# Power2.net
KiCad netlist of a schematic drawn in Altium Designer
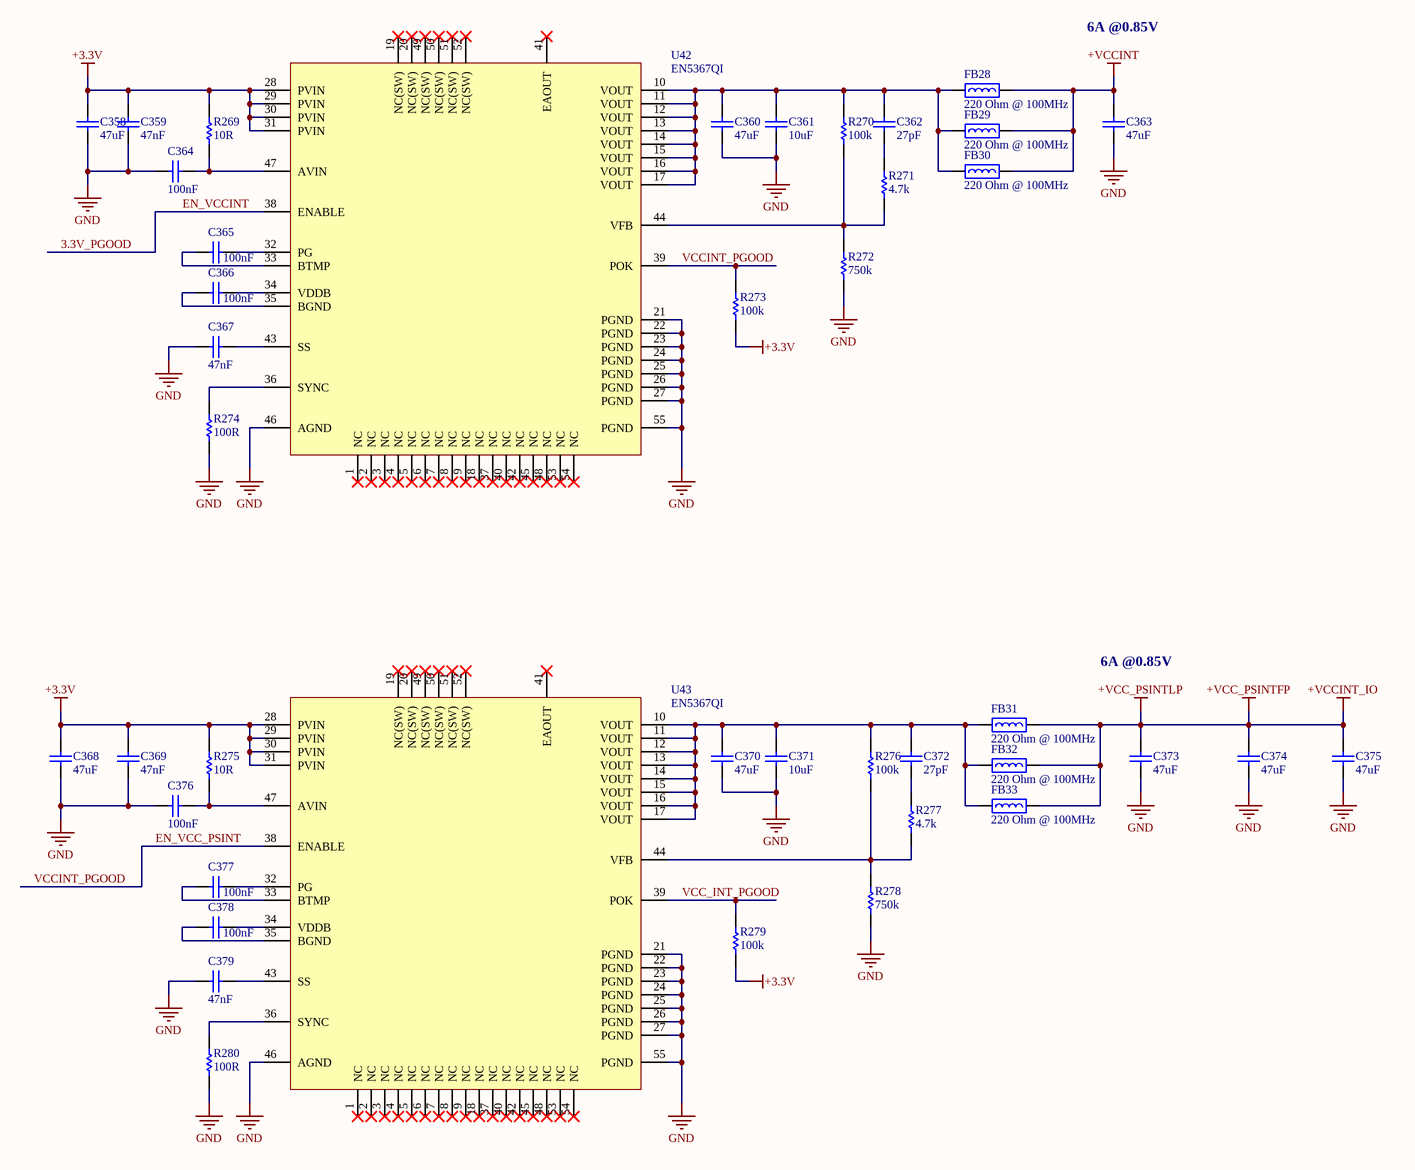
[diagram p0: Power2.SchDoc]

(export (version "E")
  (design (tool "Eeschema 10.0.6"))
  (components
    (comp (ref "C358")
      (value "47uF")
      (footprint "CAPC3216L_1206")
      (description "CAP CER 47UF 25V X5R 1206")
      (fields (field (name "VOLTAGE") "25V") (field (name "TOLERANCE") "20%"))
      (libsource (lib "Ultrascale_SchLib") (part "CAPCER1206X5R47U25V_20T"))
    )
    (comp (ref "C359")
      (value "47nF")
      (footprint "CAPC2012L_0805")
      (description "CAP CER 0.047UF 50V X7R 0805")
      (fields (field (name "VOLTAGE") "50V") (field (name "TOLERANCE") "10%"))
      (libsource (lib "Ultrascale_SchLib") (part "CAPCER0805X5R47N50V_10T"))
    )
    (comp (ref "C360")
      (value "47uF")
      (footprint "CAPC3216L_1206")
      (description "CAP CER 47UF 25V X5R 1206")
      (fields (field (name "VOLTAGE") "25V") (field (name "TOLERANCE") "20%"))
      (libsource (lib "Ultrascale_SchLib") (part "CAPCER1206X5R47U25V_20T"))
    )
    (comp (ref "C361")
      (value "10uF")
      (footprint "CAPC1005L_0402")
      (description "CAP CER 10UF 10V X5R 0402")
      (fields (field (name "VOLTAGE") "10V") (field (name "TOLERANCE") "20%"))
      (libsource (lib "Ultrascale_SchLib") (part "CAPCER0402X5R10U10V_20T"))
    )
    (comp (ref "C362")
      (value "27pF")
      (footprint "CAPC1005L_0402")
      (description "CAP CER 27PF 50V C0G/NP0 0402")
      (fields (field (name "VOLTAGE") "50V") (field (name "TOLERANCE") "5%"))
      (libsource (lib "Ultrascale_SchLib") (part "CAPCER0402C0G27P50V_5T"))
    )
    (comp (ref "C363")
      (value "47uF")
      (footprint "CAPC3216L_1206")
      (description "CAP CER 47UF 25V X5R 1206")
      (fields (field (name "VOLTAGE") "25V") (field (name "TOLERANCE") "20%"))
      (libsource (lib "Ultrascale_SchLib") (part "CAPCER1206X5R47U25V_20T"))
    )
    (comp (ref "C364")
      (value "100nF")
      (footprint "CAPC1005L_0402")
      (description "CAP CER 0.1UF 25V X7R 0402")
      (fields (field (name "VOLTAGE") "25V") (field (name "TOLERANCE") "10%"))
      (libsource (lib "Ultrascale_SchLib") (part "CAPCER0402X7R100N25V_10T"))
    )
    (comp (ref "C365")
      (value "100nF")
      (footprint "CAPC1005L_0402")
      (description "CAP CER 0.1UF 25V X7R 0402")
      (fields (field (name "VOLTAGE") "25V") (field (name "TOLERANCE") "10%"))
      (libsource (lib "Ultrascale_SchLib") (part "CAPCER0402X7R100N25V_10T"))
    )
    (comp (ref "C366")
      (value "100nF")
      (footprint "CAPC1005L_0402")
      (description "CAP CER 0.1UF 25V X7R 0402")
      (fields (field (name "VOLTAGE") "25V") (field (name "TOLERANCE") "10%"))
      (libsource (lib "Ultrascale_SchLib") (part "CAPCER0402X7R100N25V_10T"))
    )
    (comp (ref "C367")
      (value "47nF")
      (footprint "CAPC2012L_0805")
      (description "CAP CER 0.047UF 50V X7R 0805")
      (fields (field (name "VOLTAGE") "50V") (field (name "TOLERANCE") "10%"))
      (libsource (lib "Ultrascale_SchLib") (part "CAPCER0805X5R47N50V_10T"))
    )
    (comp (ref "C368")
      (value "47uF")
      (footprint "CAPC3216L_1206")
      (description "CAP CER 47UF 25V X5R 1206")
      (fields (field (name "VOLTAGE") "25V") (field (name "TOLERANCE") "20%"))
      (libsource (lib "Ultrascale_SchLib") (part "CAPCER1206X5R47U25V_20T"))
    )
    (comp (ref "C369")
      (value "47nF")
      (footprint "CAPC2012L_0805")
      (description "CAP CER 0.047UF 50V X7R 0805")
      (fields (field (name "VOLTAGE") "50V") (field (name "TOLERANCE") "10%"))
      (libsource (lib "Ultrascale_SchLib") (part "CAPCER0805X5R47N50V_10T"))
    )
    (comp (ref "C370")
      (value "47uF")
      (footprint "CAPC3216L_1206")
      (description "CAP CER 47UF 25V X5R 1206")
      (fields (field (name "VOLTAGE") "25V") (field (name "TOLERANCE") "20%"))
      (libsource (lib "Ultrascale_SchLib") (part "CAPCER1206X5R47U25V_20T"))
    )
    (comp (ref "C371")
      (value "10uF")
      (footprint "CAPC1005L_0402")
      (description "CAP CER 10UF 10V X5R 0402")
      (fields (field (name "VOLTAGE") "10V") (field (name "TOLERANCE") "20%"))
      (libsource (lib "Ultrascale_SchLib") (part "CAPCER0402X5R10U10V_20T"))
    )
    (comp (ref "C372")
      (value "27pF")
      (footprint "CAPC1005L_0402")
      (description "CAP CER 27PF 50V C0G/NP0 0402")
      (fields (field (name "VOLTAGE") "50V") (field (name "TOLERANCE") "5%"))
      (libsource (lib "Ultrascale_SchLib") (part "CAPCER0402C0G27P50V_5T"))
    )
    (comp (ref "C373")
      (value "47uF")
      (footprint "CAPC3216L_1206")
      (description "CAP CER 47UF 25V X5R 1206")
      (fields (field (name "VOLTAGE") "25V") (field (name "TOLERANCE") "20%"))
      (libsource (lib "Ultrascale_SchLib") (part "CAPCER1206X5R47U25V_20T"))
    )
    (comp (ref "C374")
      (value "47uF")
      (footprint "CAPC3216L_1206")
      (description "CAP CER 47UF 25V X5R 1206")
      (fields (field (name "VOLTAGE") "25V") (field (name "TOLERANCE") "20%"))
      (libsource (lib "Ultrascale_SchLib") (part "CAPCER1206X5R47U25V_20T"))
    )
    (comp (ref "C375")
      (value "47uF")
      (footprint "CAPC3216L_1206")
      (description "CAP CER 47UF 25V X5R 1206")
      (fields (field (name "VOLTAGE") "25V") (field (name "TOLERANCE") "20%"))
      (libsource (lib "Ultrascale_SchLib") (part "CAPCER1206X5R47U25V_20T"))
    )
    (comp (ref "C376")
      (value "100nF")
      (footprint "CAPC1005L_0402")
      (description "CAP CER 0.1UF 25V X7R 0402")
      (fields (field (name "VOLTAGE") "25V") (field (name "TOLERANCE") "10%"))
      (libsource (lib "Ultrascale_SchLib") (part "CAPCER0402X7R100N25V_10T"))
    )
    (comp (ref "C377")
      (value "100nF")
      (footprint "CAPC1005L_0402")
      (description "CAP CER 0.1UF 25V X7R 0402")
      (fields (field (name "VOLTAGE") "25V") (field (name "TOLERANCE") "10%"))
      (libsource (lib "Ultrascale_SchLib") (part "CAPCER0402X7R100N25V_10T"))
    )
    (comp (ref "C378")
      (value "100nF")
      (footprint "CAPC1005L_0402")
      (description "CAP CER 0.1UF 25V X7R 0402")
      (fields (field (name "VOLTAGE") "25V") (field (name "TOLERANCE") "10%"))
      (libsource (lib "Ultrascale_SchLib") (part "CAPCER0402X7R100N25V_10T"))
    )
    (comp (ref "C379")
      (value "47nF")
      (footprint "CAPC2012L_0805")
      (description "CAP CER 0.047UF 50V X7R 0805")
      (fields (field (name "VOLTAGE") "50V") (field (name "TOLERANCE") "10%"))
      (libsource (lib "Ultrascale_SchLib") (part "CAPCER0805X5R47N50V_10T"))
    )
    (comp (ref "FB28")
      (value "BEAD0603_220_2A5_40M")
      (footprint "INDC1608N_0603")
      (description "FERRITE BEAD 220 OHM 0603 1LN")
      (fields (field (name "IMPEDANCE @ FREQUENCY") "220 Ohm @ 100MHz"))
      (libsource (lib "Ultrascale_SchLib") (part "BEAD0603_220_2A5_40M"))
    )
    (comp (ref "FB29")
      (value "BEAD0603_220_2A5_40M")
      (footprint "INDC1608N_0603")
      (description "FERRITE BEAD 220 OHM 0603 1LN")
      (fields (field (name "IMPEDANCE @ FREQUENCY") "220 Ohm @ 100MHz"))
      (libsource (lib "Ultrascale_SchLib") (part "BEAD0603_220_2A5_40M"))
    )
    (comp (ref "FB30")
      (value "BEAD0603_220_2A5_40M")
      (footprint "INDC1608N_0603")
      (description "FERRITE BEAD 220 OHM 0603 1LN")
      (fields (field (name "IMPEDANCE @ FREQUENCY") "220 Ohm @ 100MHz"))
      (libsource (lib "Ultrascale_SchLib") (part "BEAD0603_220_2A5_40M"))
    )
    (comp (ref "FB31")
      (value "BEAD0603_220_2A5_40M")
      (footprint "INDC1608N_0603")
      (description "FERRITE BEAD 220 OHM 0603 1LN")
      (fields (field (name "IMPEDANCE @ FREQUENCY") "220 Ohm @ 100MHz"))
      (libsource (lib "Ultrascale_SchLib") (part "BEAD0603_220_2A5_40M"))
    )
    (comp (ref "FB32")
      (value "BEAD0603_220_2A5_40M")
      (footprint "INDC1608N_0603")
      (description "FERRITE BEAD 220 OHM 0603 1LN")
      (fields (field (name "IMPEDANCE @ FREQUENCY") "220 Ohm @ 100MHz"))
      (libsource (lib "Ultrascale_SchLib") (part "BEAD0603_220_2A5_40M"))
    )
    (comp (ref "FB33")
      (value "BEAD0603_220_2A5_40M")
      (footprint "INDC1608N_0603")
      (description "FERRITE BEAD 220 OHM 0603 1LN")
      (fields (field (name "IMPEDANCE @ FREQUENCY") "220 Ohm @ 100MHz"))
      (libsource (lib "Ultrascale_SchLib") (part "BEAD0603_220_2A5_40M"))
    )
    (comp (ref "R269")
      (value "10R")
      (footprint "RESC1005L_0402")
      (description "RES SMD 10 OHM 1% 1/10W 0402")
      (fields (field (name "POWER") "1/10W") (field (name "TOLERANCE") "1%"))
      (libsource (lib "Ultrascale_SchLib") (part "RES0402_10R_0W1_1T"))
    )
    (comp (ref "R270")
      (value "100k")
      (footprint "RESC1005L_0402")
      (description "RES SMD 100K OHM 1% 1/5W 0402")
      (fields (field (name "POWER") "1/5W") (field (name "TOLERANCE") "1%"))
      (libsource (lib "Ultrascale_SchLib") (part "RES0402_100K_0W2_1T"))
    )
    (comp (ref "R271")
      (value "4.7k")
      (footprint "RESC1005L_0402")
      (description "RES SMD 4.7K OHM 1% 1/10W 0402")
      (fields (field (name "POWER") "1/10W") (field (name "TOLERANCE") "1%"))
      (libsource (lib "Ultrascale_SchLib") (part "RES0402_4K7_0W1_1T"))
    )
    (comp (ref "R272")
      (value "750k")
      (footprint "RESC1005L_0402")
      (description "RES SMD 750K OHM 1% 1/10W 0402")
      (fields (field (name "POWER") "1/10W") (field (name "TOLERANCE") "1%"))
      (libsource (lib "Ultrascale_SchLib") (part "RES0402_750K_0W1_1T"))
    )
    (comp (ref "R273")
      (value "100k")
      (footprint "RESC1005L_0402")
      (description "RES SMD 100K OHM 1% 1/5W 0402")
      (fields (field (name "POWER") "1/5W") (field (name "TOLERANCE") "1%"))
      (libsource (lib "Ultrascale_SchLib") (part "RES0402_100K_0W2_1T"))
    )
    (comp (ref "R274")
      (value "100R")
      (footprint "RESC1005L_0402")
      (description "RES SMD 100 OHM 1% 1/10W 0402")
      (fields (field (name "POWER") "1/10W") (field (name "TOLERANCE") "1%"))
      (libsource (lib "Ultrascale_SchLib") (part "RES0402_100R_0W1_1T"))
    )
    (comp (ref "R275")
      (value "10R")
      (footprint "RESC1005L_0402")
      (description "RES SMD 10 OHM 1% 1/10W 0402")
      (fields (field (name "POWER") "1/10W") (field (name "TOLERANCE") "1%"))
      (libsource (lib "Ultrascale_SchLib") (part "RES0402_10R_0W1_1T"))
    )
    (comp (ref "R276")
      (value "100k")
      (footprint "RESC1005L_0402")
      (description "RES SMD 100K OHM 1% 1/5W 0402")
      (fields (field (name "POWER") "1/5W") (field (name "TOLERANCE") "1%"))
      (libsource (lib "Ultrascale_SchLib") (part "RES0402_100K_0W2_1T"))
    )
    (comp (ref "R277")
      (value "4.7k")
      (footprint "RESC1005L_0402")
      (description "RES SMD 4.7K OHM 1% 1/10W 0402")
      (fields (field (name "POWER") "1/10W") (field (name "TOLERANCE") "1%"))
      (libsource (lib "Ultrascale_SchLib") (part "RES0402_4K7_0W1_1T"))
    )
    (comp (ref "R278")
      (value "750k")
      (footprint "RESC1005L_0402")
      (description "RES SMD 750K OHM 1% 1/10W 0402")
      (fields (field (name "POWER") "1/10W") (field (name "TOLERANCE") "1%"))
      (libsource (lib "Ultrascale_SchLib") (part "RES0402_750K_0W1_1T"))
    )
    (comp (ref "R279")
      (value "100k")
      (footprint "RESC1005L_0402")
      (description "RES SMD 100K OHM 1% 1/5W 0402")
      (fields (field (name "POWER") "1/5W") (field (name "TOLERANCE") "1%"))
      (libsource (lib "Ultrascale_SchLib") (part "RES0402_100K_0W2_1T"))
    )
    (comp (ref "R280")
      (value "100R")
      (footprint "RESC1005L_0402")
      (description "RES SMD 100 OHM 1% 1/10W 0402")
      (fields (field (name "POWER") "1/10W") (field (name "TOLERANCE") "1%"))
      (libsource (lib "Ultrascale_SchLib") (part "RES0402_100R_0W1_1T"))
    )
    (comp (ref "U42")
      (value "EN5367QI")
      (footprint "QFN54-EN5367QI")
      (description "DC/DC CONVERTER 0.6-4.9V 29W")
      (libsource (lib "Ultrascale_SchLib") (part "EN5367QI"))
    )
    (comp (ref "U43")
      (value "EN5367QI")
      (footprint "QFN54-EN5367QI")
      (description "DC/DC CONVERTER 0.6-4.9V 29W")
      (libsource (lib "Ultrascale_SchLib") (part "EN5367QI"))
    )
  )
  (nets
    (net (code "1") (name "+3.3V") (class "Default")
      (node (ref "C358") (pin "2") (pinfunction "2_2") (pintype "passive"))
      (node (ref "C359") (pin "2") (pinfunction "2_2") (pintype "passive"))
      (node (ref "C368") (pin "2") (pinfunction "2_2") (pintype "passive"))
      (node (ref "C369") (pin "2") (pinfunction "2_2") (pintype "passive"))
      (node (ref "R269") (pin "2") (pinfunction "2_2") (pintype "passive"))
      (node (ref "R273") (pin "2") (pinfunction "2_2") (pintype "passive"))
      (node (ref "R275") (pin "2") (pinfunction "2_2") (pintype "passive"))
      (node (ref "R279") (pin "2") (pinfunction "2_2") (pintype "passive"))
      (node (ref "U42") (pin "28") (pinfunction "PVIN_28") (pintype "power_in"))
      (node (ref "U42") (pin "29") (pinfunction "PVIN_29") (pintype "power_in"))
      (node (ref "U42") (pin "30") (pinfunction "PVIN_30") (pintype "power_in"))
      (node (ref "U42") (pin "31") (pinfunction "PVIN_31") (pintype "power_in"))
      (node (ref "U43") (pin "28") (pinfunction "PVIN_28") (pintype "power_in"))
      (node (ref "U43") (pin "29") (pinfunction "PVIN_29") (pintype "power_in"))
      (node (ref "U43") (pin "30") (pinfunction "PVIN_30") (pintype "power_in"))
      (node (ref "U43") (pin "31") (pinfunction "PVIN_31") (pintype "power_in"))
    )
    (net (code "2") (name "+VCCINT") (class "Default")
      (node (ref "C363") (pin "2") (pinfunction "2_2") (pintype "passive"))
      (node (ref "FB28") (pin "2") (pinfunction "2_2") (pintype "passive"))
      (node (ref "FB29") (pin "2") (pinfunction "2_2") (pintype "passive"))
      (node (ref "FB30") (pin "2") (pinfunction "2_2") (pintype "passive"))
    )
    (net (code "3") (name "+VCCINT_IO") (class "Default")
      (node (ref "C373") (pin "2") (pinfunction "2_2") (pintype "passive"))
      (node (ref "C374") (pin "2") (pinfunction "2_2") (pintype "passive"))
      (node (ref "C375") (pin "2") (pinfunction "2_2") (pintype "passive"))
      (node (ref "FB31") (pin "2") (pinfunction "2_2") (pintype "passive"))
      (node (ref "FB32") (pin "2") (pinfunction "2_2") (pintype "passive"))
      (node (ref "FB33") (pin "2") (pinfunction "2_2") (pintype "passive"))
    )
    (net (code "4") (name "/3.3V_PGOOD") (class "Default")
      (node (ref "U42") (pin "38") (pinfunction "ENABLE_38") (pintype "power_in"))
    )
    (net (code "5") (name "/EN_VCC_PSINT") (class "Default")
      (node (ref "R273") (pin "1") (pinfunction "1_1") (pintype "passive"))
      (node (ref "U42") (pin "39") (pinfunction "POK_39") (pintype "power_in"))
      (node (ref "U43") (pin "38") (pinfunction "ENABLE_38") (pintype "power_in"))
    )
    (net (code "6") (name "/VCC_INT_PGOOD") (class "Default")
      (node (ref "R279") (pin "1") (pinfunction "1_1") (pintype "passive"))
      (node (ref "U43") (pin "39") (pinfunction "POK_39") (pintype "power_in"))
    )
    (net (code "7") (name "GND") (class "Default")
      (node (ref "C358") (pin "1") (pinfunction "1_1") (pintype "passive"))
      (node (ref "C359") (pin "1") (pinfunction "1_1") (pintype "passive"))
      (node (ref "C360") (pin "1") (pinfunction "1_1") (pintype "passive"))
      (node (ref "C361") (pin "1") (pinfunction "1_1") (pintype "passive"))
      (node (ref "C363") (pin "1") (pinfunction "1_1") (pintype "passive"))
      (node (ref "C364") (pin "2") (pinfunction "2_2") (pintype "passive"))
      (node (ref "C367") (pin "2") (pinfunction "2_2") (pintype "passive"))
      (node (ref "C368") (pin "1") (pinfunction "1_1") (pintype "passive"))
      (node (ref "C369") (pin "1") (pinfunction "1_1") (pintype "passive"))
      (node (ref "C370") (pin "1") (pinfunction "1_1") (pintype "passive"))
      (node (ref "C371") (pin "1") (pinfunction "1_1") (pintype "passive"))
      (node (ref "C373") (pin "1") (pinfunction "1_1") (pintype "passive"))
      (node (ref "C374") (pin "1") (pinfunction "1_1") (pintype "passive"))
      (node (ref "C375") (pin "1") (pinfunction "1_1") (pintype "passive"))
      (node (ref "C376") (pin "2") (pinfunction "2_2") (pintype "passive"))
      (node (ref "C379") (pin "2") (pinfunction "2_2") (pintype "passive"))
      (node (ref "R272") (pin "1") (pinfunction "1_1") (pintype "passive"))
      (node (ref "R274") (pin "2") (pinfunction "2_2") (pintype "passive"))
      (node (ref "R278") (pin "1") (pinfunction "1_1") (pintype "passive"))
      (node (ref "R280") (pin "2") (pinfunction "2_2") (pintype "passive"))
      (node (ref "U42") (pin "21") (pinfunction "PGND_21") (pintype "power_in"))
      (node (ref "U42") (pin "22") (pinfunction "PGND_22") (pintype "power_in"))
      (node (ref "U42") (pin "23") (pinfunction "PGND_23") (pintype "power_in"))
      (node (ref "U42") (pin "24") (pinfunction "PGND_24") (pintype "power_in"))
      (node (ref "U42") (pin "25") (pinfunction "PGND_25") (pintype "power_in"))
      (node (ref "U42") (pin "26") (pinfunction "PGND_26") (pintype "power_in"))
      (node (ref "U42") (pin "27") (pinfunction "PGND_27") (pintype "power_in"))
      (node (ref "U42") (pin "46") (pinfunction "AGND_46") (pintype "power_in"))
      (node (ref "U42") (pin "55") (pinfunction "PGND_55") (pintype "power_in"))
      (node (ref "U43") (pin "21") (pinfunction "PGND_21") (pintype "power_in"))
      (node (ref "U43") (pin "22") (pinfunction "PGND_22") (pintype "power_in"))
      (node (ref "U43") (pin "23") (pinfunction "PGND_23") (pintype "power_in"))
      (node (ref "U43") (pin "24") (pinfunction "PGND_24") (pintype "power_in"))
      (node (ref "U43") (pin "25") (pinfunction "PGND_25") (pintype "power_in"))
      (node (ref "U43") (pin "26") (pinfunction "PGND_26") (pintype "power_in"))
      (node (ref "U43") (pin "27") (pinfunction "PGND_27") (pintype "power_in"))
      (node (ref "U43") (pin "46") (pinfunction "AGND_46") (pintype "power_in"))
      (node (ref "U43") (pin "55") (pinfunction "PGND_55") (pintype "power_in"))
    )
    (net (code "8") (name "Net-(C360-Pad2)") (class "Default")
      (node (ref "C360") (pin "2") (pinfunction "2_2") (pintype "passive"))
      (node (ref "C361") (pin "2") (pinfunction "2_2") (pintype "passive"))
      (node (ref "C362") (pin "2") (pinfunction "2_2") (pintype "passive"))
      (node (ref "FB28") (pin "1") (pinfunction "1_1") (pintype "passive"))
      (node (ref "FB29") (pin "1") (pinfunction "1_1") (pintype "passive"))
      (node (ref "FB30") (pin "1") (pinfunction "1_1") (pintype "passive"))
      (node (ref "R270") (pin "2") (pinfunction "2_2") (pintype "passive"))
      (node (ref "U42") (pin "10") (pinfunction "VOUT_10") (pintype "power_in"))
      (node (ref "U42") (pin "11") (pinfunction "VOUT_11") (pintype "power_in"))
      (node (ref "U42") (pin "12") (pinfunction "VOUT_12") (pintype "power_in"))
      (node (ref "U42") (pin "13") (pinfunction "VOUT_13") (pintype "power_in"))
      (node (ref "U42") (pin "14") (pinfunction "VOUT_14") (pintype "power_in"))
      (node (ref "U42") (pin "15") (pinfunction "VOUT_15") (pintype "power_in"))
      (node (ref "U42") (pin "16") (pinfunction "VOUT_16") (pintype "power_in"))
      (node (ref "U42") (pin "17") (pinfunction "VOUT_17") (pintype "power_in"))
    )
    (net (code "9") (name "Net-(C362-Pad1)") (class "Default")
      (node (ref "C362") (pin "1") (pinfunction "1_1") (pintype "passive"))
      (node (ref "R271") (pin "2") (pinfunction "2_2") (pintype "passive"))
    )
    (net (code "10") (name "Net-(C370-Pad2)") (class "Default")
      (node (ref "C370") (pin "2") (pinfunction "2_2") (pintype "passive"))
      (node (ref "C371") (pin "2") (pinfunction "2_2") (pintype "passive"))
      (node (ref "C372") (pin "2") (pinfunction "2_2") (pintype "passive"))
      (node (ref "FB31") (pin "1") (pinfunction "1_1") (pintype "passive"))
      (node (ref "FB32") (pin "1") (pinfunction "1_1") (pintype "passive"))
      (node (ref "FB33") (pin "1") (pinfunction "1_1") (pintype "passive"))
      (node (ref "R276") (pin "2") (pinfunction "2_2") (pintype "passive"))
      (node (ref "U43") (pin "10") (pinfunction "VOUT_10") (pintype "power_in"))
      (node (ref "U43") (pin "11") (pinfunction "VOUT_11") (pintype "power_in"))
      (node (ref "U43") (pin "12") (pinfunction "VOUT_12") (pintype "power_in"))
      (node (ref "U43") (pin "13") (pinfunction "VOUT_13") (pintype "power_in"))
      (node (ref "U43") (pin "14") (pinfunction "VOUT_14") (pintype "power_in"))
      (node (ref "U43") (pin "15") (pinfunction "VOUT_15") (pintype "power_in"))
      (node (ref "U43") (pin "16") (pinfunction "VOUT_16") (pintype "power_in"))
      (node (ref "U43") (pin "17") (pinfunction "VOUT_17") (pintype "power_in"))
    )
    (net (code "11") (name "Net-(C372-Pad1)") (class "Default")
      (node (ref "C372") (pin "1") (pinfunction "1_1") (pintype "passive"))
      (node (ref "R277") (pin "2") (pinfunction "2_2") (pintype "passive"))
    )
    (net (code "12") (name "Net-(U42-AVIN)") (class "Default")
      (node (ref "C364") (pin "1") (pinfunction "1_1") (pintype "passive"))
      (node (ref "R269") (pin "1") (pinfunction "1_1") (pintype "passive"))
      (node (ref "U42") (pin "47") (pinfunction "AVIN_47") (pintype "power_in"))
    )
    (net (code "13") (name "Net-(U42-BGND)") (class "Default")
      (node (ref "C366") (pin "2") (pinfunction "2_2") (pintype "passive"))
      (node (ref "U42") (pin "35") (pinfunction "BGND_35") (pintype "power_in"))
    )
    (net (code "14") (name "Net-(U42-BTMP)") (class "Default")
      (node (ref "C365") (pin "2") (pinfunction "2_2") (pintype "passive"))
      (node (ref "U42") (pin "33") (pinfunction "BTMP_33") (pintype "power_in"))
    )
    (net (code "15") (name "Net-(U42-PG)") (class "Default")
      (node (ref "C365") (pin "1") (pinfunction "1_1") (pintype "passive"))
      (node (ref "U42") (pin "32") (pinfunction "PG_32") (pintype "power_in"))
    )
    (net (code "16") (name "Net-(U42-SS)") (class "Default")
      (node (ref "C367") (pin "1") (pinfunction "1_1") (pintype "passive"))
      (node (ref "U42") (pin "43") (pinfunction "SS_43") (pintype "power_in"))
    )
    (net (code "17") (name "Net-(U42-SYNC)") (class "Default")
      (node (ref "R274") (pin "1") (pinfunction "1_1") (pintype "passive"))
      (node (ref "U42") (pin "36") (pinfunction "SYNC_36") (pintype "power_in"))
    )
    (net (code "18") (name "Net-(U42-VDDB)") (class "Default")
      (node (ref "C366") (pin "1") (pinfunction "1_1") (pintype "passive"))
      (node (ref "U42") (pin "34") (pinfunction "VDDB_34") (pintype "power_in"))
    )
    (net (code "19") (name "Net-(U42-VFB)") (class "Default")
      (node (ref "R270") (pin "1") (pinfunction "1_1") (pintype "passive"))
      (node (ref "R271") (pin "1") (pinfunction "1_1") (pintype "passive"))
      (node (ref "R272") (pin "2") (pinfunction "2_2") (pintype "passive"))
      (node (ref "U42") (pin "44") (pinfunction "VFB_44") (pintype "power_in"))
    )
    (net (code "20") (name "Net-(U43-AVIN)") (class "Default")
      (node (ref "C376") (pin "1") (pinfunction "1_1") (pintype "passive"))
      (node (ref "R275") (pin "1") (pinfunction "1_1") (pintype "passive"))
      (node (ref "U43") (pin "47") (pinfunction "AVIN_47") (pintype "power_in"))
    )
    (net (code "21") (name "Net-(U43-BGND)") (class "Default")
      (node (ref "C378") (pin "2") (pinfunction "2_2") (pintype "passive"))
      (node (ref "U43") (pin "35") (pinfunction "BGND_35") (pintype "power_in"))
    )
    (net (code "22") (name "Net-(U43-BTMP)") (class "Default")
      (node (ref "C377") (pin "2") (pinfunction "2_2") (pintype "passive"))
      (node (ref "U43") (pin "33") (pinfunction "BTMP_33") (pintype "power_in"))
    )
    (net (code "23") (name "Net-(U43-PG)") (class "Default")
      (node (ref "C377") (pin "1") (pinfunction "1_1") (pintype "passive"))
      (node (ref "U43") (pin "32") (pinfunction "PG_32") (pintype "power_in"))
    )
    (net (code "24") (name "Net-(U43-SS)") (class "Default")
      (node (ref "C379") (pin "1") (pinfunction "1_1") (pintype "passive"))
      (node (ref "U43") (pin "43") (pinfunction "SS_43") (pintype "power_in"))
    )
    (net (code "25") (name "Net-(U43-SYNC)") (class "Default")
      (node (ref "R280") (pin "1") (pinfunction "1_1") (pintype "passive"))
      (node (ref "U43") (pin "36") (pinfunction "SYNC_36") (pintype "power_in"))
    )
    (net (code "26") (name "Net-(U43-VDDB)") (class "Default")
      (node (ref "C378") (pin "1") (pinfunction "1_1") (pintype "passive"))
      (node (ref "U43") (pin "34") (pinfunction "VDDB_34") (pintype "power_in"))
    )
    (net (code "27") (name "Net-(U43-VFB)") (class "Default")
      (node (ref "R276") (pin "1") (pinfunction "1_1") (pintype "passive"))
      (node (ref "R277") (pin "1") (pinfunction "1_1") (pintype "passive"))
      (node (ref "R278") (pin "2") (pinfunction "2_2") (pintype "passive"))
      (node (ref "U43") (pin "44") (pinfunction "VFB_44") (pintype "power_in"))
    )
    (net (code "28") (name "unconnected-(U42-EAOUT-Pad41)") (class "Default")
      (node (ref "U42") (pin "41") (pinfunction "EAOUT_41") (pintype "power_in+no_connect"))
    )
    (net (code "29") (name "unconnected-(U42-NC(SW)-Pad19)") (class "Default")
      (node (ref "U42") (pin "19") (pinfunction "NC(SW)_19") (pintype "power_in+no_connect"))
    )
    (net (code "30") (name "unconnected-(U42-NC(SW)-Pad20)") (class "Default")
      (node (ref "U42") (pin "20") (pinfunction "NC(SW)_20") (pintype "power_in+no_connect"))
    )
    (net (code "31") (name "unconnected-(U42-NC(SW)-Pad49)") (class "Default")
      (node (ref "U42") (pin "49") (pinfunction "NC(SW)_49") (pintype "power_in+no_connect"))
    )
    (net (code "32") (name "unconnected-(U42-NC(SW)-Pad50)") (class "Default")
      (node (ref "U42") (pin "50") (pinfunction "NC(SW)_50") (pintype "power_in+no_connect"))
    )
    (net (code "33") (name "unconnected-(U42-NC(SW)-Pad51)") (class "Default")
      (node (ref "U42") (pin "51") (pinfunction "NC(SW)_51") (pintype "power_in+no_connect"))
    )
    (net (code "34") (name "unconnected-(U42-NC(SW)-Pad52)") (class "Default")
      (node (ref "U42") (pin "52") (pinfunction "NC(SW)_52") (pintype "power_in+no_connect"))
    )
    (net (code "35") (name "unconnected-(U42-NC-Pad1)") (class "Default")
      (node (ref "U42") (pin "1") (pinfunction "NC_1") (pintype "power_in+no_connect"))
    )
    (net (code "36") (name "unconnected-(U42-NC-Pad2)") (class "Default")
      (node (ref "U42") (pin "2") (pinfunction "NC_2") (pintype "power_in+no_connect"))
    )
    (net (code "37") (name "unconnected-(U42-NC-Pad3)") (class "Default")
      (node (ref "U42") (pin "3") (pinfunction "NC_3") (pintype "power_in+no_connect"))
    )
    (net (code "38") (name "unconnected-(U42-NC-Pad4)") (class "Default")
      (node (ref "U42") (pin "4") (pinfunction "NC_4") (pintype "power_in+no_connect"))
    )
    (net (code "39") (name "unconnected-(U42-NC-Pad5)") (class "Default")
      (node (ref "U42") (pin "5") (pinfunction "NC_5") (pintype "power_in+no_connect"))
    )
    (net (code "40") (name "unconnected-(U42-NC-Pad6)") (class "Default")
      (node (ref "U42") (pin "6") (pinfunction "NC_6") (pintype "power_in+no_connect"))
    )
    (net (code "41") (name "unconnected-(U42-NC-Pad7)") (class "Default")
      (node (ref "U42") (pin "7") (pinfunction "NC_7") (pintype "power_in+no_connect"))
    )
    (net (code "42") (name "unconnected-(U42-NC-Pad8)") (class "Default")
      (node (ref "U42") (pin "8") (pinfunction "NC_8") (pintype "power_in+no_connect"))
    )
    (net (code "43") (name "unconnected-(U42-NC-Pad9)") (class "Default")
      (node (ref "U42") (pin "9") (pinfunction "NC_9") (pintype "power_in+no_connect"))
    )
    (net (code "44") (name "unconnected-(U42-NC-Pad18)") (class "Default")
      (node (ref "U42") (pin "18") (pinfunction "NC_18") (pintype "power_in+no_connect"))
    )
    (net (code "45") (name "unconnected-(U42-NC-Pad37)") (class "Default")
      (node (ref "U42") (pin "37") (pinfunction "NC_37") (pintype "power_in+no_connect"))
    )
    (net (code "46") (name "unconnected-(U42-NC-Pad40)") (class "Default")
      (node (ref "U42") (pin "40") (pinfunction "NC_40") (pintype "power_in+no_connect"))
    )
    (net (code "47") (name "unconnected-(U42-NC-Pad42)") (class "Default")
      (node (ref "U42") (pin "42") (pinfunction "NC_42") (pintype "power_in+no_connect"))
    )
    (net (code "48") (name "unconnected-(U42-NC-Pad45)") (class "Default")
      (node (ref "U42") (pin "45") (pinfunction "NC_45") (pintype "power_in+no_connect"))
    )
    (net (code "49") (name "unconnected-(U42-NC-Pad48)") (class "Default")
      (node (ref "U42") (pin "48") (pinfunction "NC_48") (pintype "power_in+no_connect"))
    )
    (net (code "50") (name "unconnected-(U42-NC-Pad53)") (class "Default")
      (node (ref "U42") (pin "53") (pinfunction "NC_53") (pintype "power_in+no_connect"))
    )
    (net (code "51") (name "unconnected-(U42-NC-Pad54)") (class "Default")
      (node (ref "U42") (pin "54") (pinfunction "NC_54") (pintype "power_in+no_connect"))
    )
    (net (code "52") (name "unconnected-(U43-EAOUT-Pad41)") (class "Default")
      (node (ref "U43") (pin "41") (pinfunction "EAOUT_41") (pintype "power_in+no_connect"))
    )
    (net (code "53") (name "unconnected-(U43-NC(SW)-Pad19)") (class "Default")
      (node (ref "U43") (pin "19") (pinfunction "NC(SW)_19") (pintype "power_in+no_connect"))
    )
    (net (code "54") (name "unconnected-(U43-NC(SW)-Pad20)") (class "Default")
      (node (ref "U43") (pin "20") (pinfunction "NC(SW)_20") (pintype "power_in+no_connect"))
    )
    (net (code "55") (name "unconnected-(U43-NC(SW)-Pad49)") (class "Default")
      (node (ref "U43") (pin "49") (pinfunction "NC(SW)_49") (pintype "power_in+no_connect"))
    )
    (net (code "56") (name "unconnected-(U43-NC(SW)-Pad50)") (class "Default")
      (node (ref "U43") (pin "50") (pinfunction "NC(SW)_50") (pintype "power_in+no_connect"))
    )
    (net (code "57") (name "unconnected-(U43-NC(SW)-Pad51)") (class "Default")
      (node (ref "U43") (pin "51") (pinfunction "NC(SW)_51") (pintype "power_in+no_connect"))
    )
    (net (code "58") (name "unconnected-(U43-NC(SW)-Pad52)") (class "Default")
      (node (ref "U43") (pin "52") (pinfunction "NC(SW)_52") (pintype "power_in+no_connect"))
    )
    (net (code "59") (name "unconnected-(U43-NC-Pad1)") (class "Default")
      (node (ref "U43") (pin "1") (pinfunction "NC_1") (pintype "power_in+no_connect"))
    )
    (net (code "60") (name "unconnected-(U43-NC-Pad2)") (class "Default")
      (node (ref "U43") (pin "2") (pinfunction "NC_2") (pintype "power_in+no_connect"))
    )
    (net (code "61") (name "unconnected-(U43-NC-Pad3)") (class "Default")
      (node (ref "U43") (pin "3") (pinfunction "NC_3") (pintype "power_in+no_connect"))
    )
    (net (code "62") (name "unconnected-(U43-NC-Pad4)") (class "Default")
      (node (ref "U43") (pin "4") (pinfunction "NC_4") (pintype "power_in+no_connect"))
    )
    (net (code "63") (name "unconnected-(U43-NC-Pad5)") (class "Default")
      (node (ref "U43") (pin "5") (pinfunction "NC_5") (pintype "power_in+no_connect"))
    )
    (net (code "64") (name "unconnected-(U43-NC-Pad6)") (class "Default")
      (node (ref "U43") (pin "6") (pinfunction "NC_6") (pintype "power_in+no_connect"))
    )
    (net (code "65") (name "unconnected-(U43-NC-Pad7)") (class "Default")
      (node (ref "U43") (pin "7") (pinfunction "NC_7") (pintype "power_in+no_connect"))
    )
    (net (code "66") (name "unconnected-(U43-NC-Pad8)") (class "Default")
      (node (ref "U43") (pin "8") (pinfunction "NC_8") (pintype "power_in+no_connect"))
    )
    (net (code "67") (name "unconnected-(U43-NC-Pad9)") (class "Default")
      (node (ref "U43") (pin "9") (pinfunction "NC_9") (pintype "power_in+no_connect"))
    )
    (net (code "68") (name "unconnected-(U43-NC-Pad18)") (class "Default")
      (node (ref "U43") (pin "18") (pinfunction "NC_18") (pintype "power_in+no_connect"))
    )
    (net (code "69") (name "unconnected-(U43-NC-Pad37)") (class "Default")
      (node (ref "U43") (pin "37") (pinfunction "NC_37") (pintype "power_in+no_connect"))
    )
    (net (code "70") (name "unconnected-(U43-NC-Pad40)") (class "Default")
      (node (ref "U43") (pin "40") (pinfunction "NC_40") (pintype "power_in+no_connect"))
    )
    (net (code "71") (name "unconnected-(U43-NC-Pad42)") (class "Default")
      (node (ref "U43") (pin "42") (pinfunction "NC_42") (pintype "power_in+no_connect"))
    )
    (net (code "72") (name "unconnected-(U43-NC-Pad45)") (class "Default")
      (node (ref "U43") (pin "45") (pinfunction "NC_45") (pintype "power_in+no_connect"))
    )
    (net (code "73") (name "unconnected-(U43-NC-Pad48)") (class "Default")
      (node (ref "U43") (pin "48") (pinfunction "NC_48") (pintype "power_in+no_connect"))
    )
    (net (code "74") (name "unconnected-(U43-NC-Pad53)") (class "Default")
      (node (ref "U43") (pin "53") (pinfunction "NC_53") (pintype "power_in+no_connect"))
    )
    (net (code "75") (name "unconnected-(U43-NC-Pad54)") (class "Default")
      (node (ref "U43") (pin "54") (pinfunction "NC_54") (pintype "power_in+no_connect"))
    )
  )
)
